# DAC.net
KiCad netlist of a schematic drawn in Altium Designer
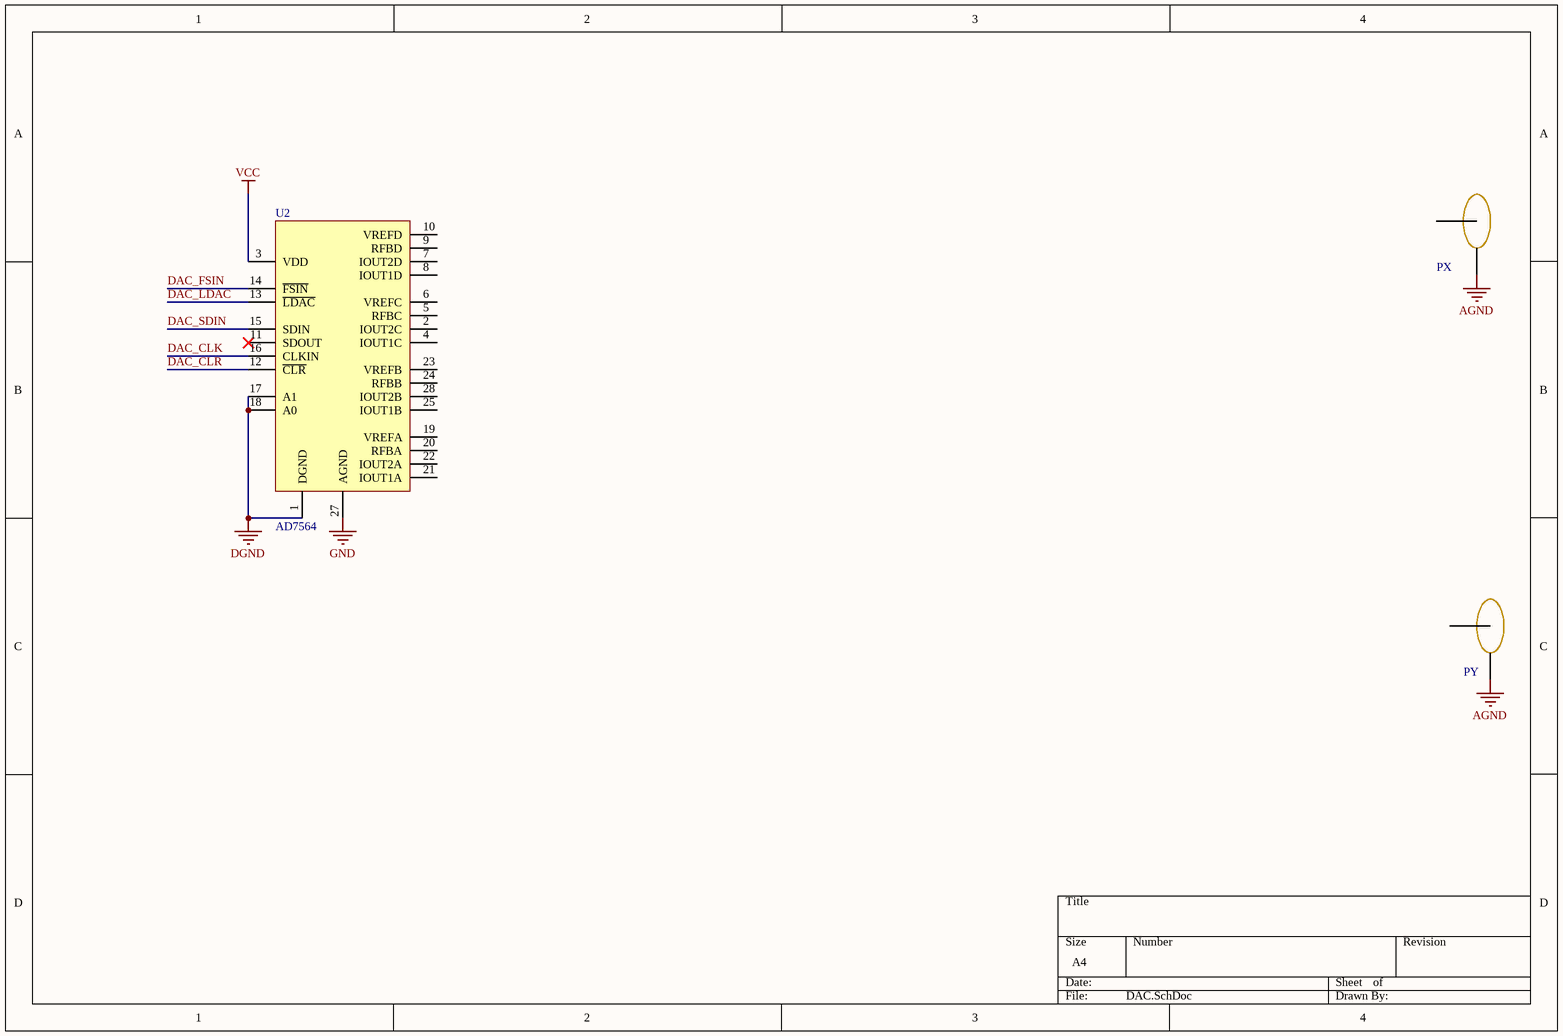
[diagram p0: DAC.SchDoc]

(export (version "E")
  (design (tool "Eeschema 10.0.6"))
  (components
    (comp (ref "PX")
      (value "PCB.SMAFRA.HT")
      (footprint "PCB.SMAFRA.HT")
      (libsource (lib "OpenSEM") (part "PCB.SMAFRA.HT"))
    )
    (comp (ref "PY")
      (value "PCB.SMAFRA.HT")
      (footprint "PCB.SMAFRA.HT")
      (libsource (lib "OpenSEM") (part "PCB.SMAFRA.HT"))
    )
    (comp (ref "U2")
      (value "AD7564")
      (footprint "AD7564")
      (description "+3.3 V/+5 V, Low Power, Quad 12-Bit DAC")
      (libsource (lib "OpenSEM") (part "AD7564"))
    )
  )
  (nets
    (net (code "1") (name "/DAC_CLK") (class "Default")
      (node (ref "U2") (pin "16") (pinfunction "CLKIN_16") (pintype "passive"))
    )
    (net (code "2") (name "/DAC_CLR") (class "Default")
      (node (ref "U2") (pin "12") (pinfunction "~{CLR}_12") (pintype "passive"))
    )
    (net (code "3") (name "/DAC_FSIN") (class "Default")
      (node (ref "U2") (pin "14") (pinfunction "~{FSIN}_14") (pintype "passive"))
    )
    (net (code "4") (name "/DAC_LDAC") (class "Default")
      (node (ref "U2") (pin "13") (pinfunction "~{LDAC}_13") (pintype "passive"))
    )
    (net (code "5") (name "/DAC_SDIN") (class "Default")
      (node (ref "U2") (pin "15") (pinfunction "SDIN_15") (pintype "passive"))
    )
    (net (code "6") (name "AGND") (class "Default")
      (node (ref "PX") (pin "S") (pinfunction "S_S") (pintype "passive"))
      (node (ref "PY") (pin "S") (pinfunction "S_S") (pintype "passive"))
    )
    (net (code "7") (name "DGND") (class "Default")
      (node (ref "U2") (pin "1") (pinfunction "DGND_1") (pintype "passive"))
      (node (ref "U2") (pin "17") (pinfunction "A1_17") (pintype "passive"))
      (node (ref "U2") (pin "18") (pinfunction "A0_18") (pintype "passive"))
    )
    (net (code "8") (name "GND") (class "Default")
      (node (ref "U2") (pin "27") (pinfunction "AGND_27") (pintype "passive"))
    )
    (net (code "9") (name "VCC") (class "Default")
      (node (ref "U2") (pin "3") (pinfunction "VDD_3") (pintype "passive"))
    )
    (net (code "10") (name "unconnected-(PX-Pad1)") (class "Default")
      (node (ref "PX") (pin "1") (pinfunction "1_1") (pintype "passive"))
    )
    (net (code "11") (name "unconnected-(PY-Pad1)") (class "Default")
      (node (ref "PY") (pin "1") (pinfunction "1_1") (pintype "passive"))
    )
    (net (code "12") (name "unconnected-(U2-IOUT1A-Pad21)") (class "Default")
      (node (ref "U2") (pin "21") (pinfunction "IOUT1A_21") (pintype "passive"))
    )
    (net (code "13") (name "unconnected-(U2-IOUT1B-Pad25)") (class "Default")
      (node (ref "U2") (pin "25") (pinfunction "IOUT1B_25") (pintype "passive"))
    )
    (net (code "14") (name "unconnected-(U2-IOUT1C-Pad4)") (class "Default")
      (node (ref "U2") (pin "4") (pinfunction "IOUT1C_4") (pintype "passive"))
    )
    (net (code "15") (name "unconnected-(U2-IOUT1D-Pad8)") (class "Default")
      (node (ref "U2") (pin "8") (pinfunction "IOUT1D_8") (pintype "passive"))
    )
    (net (code "16") (name "unconnected-(U2-IOUT2A-Pad22)") (class "Default")
      (node (ref "U2") (pin "22") (pinfunction "IOUT2A_22") (pintype "passive"))
    )
    (net (code "17") (name "unconnected-(U2-IOUT2B-Pad28)") (class "Default")
      (node (ref "U2") (pin "28") (pinfunction "IOUT2B_28") (pintype "passive"))
    )
    (net (code "18") (name "unconnected-(U2-IOUT2C-Pad2)") (class "Default")
      (node (ref "U2") (pin "2") (pinfunction "IOUT2C_2") (pintype "passive"))
    )
    (net (code "19") (name "unconnected-(U2-IOUT2D-Pad7)") (class "Default")
      (node (ref "U2") (pin "7") (pinfunction "IOUT2D_7") (pintype "passive"))
    )
    (net (code "20") (name "unconnected-(U2-RFBA-Pad20)") (class "Default")
      (node (ref "U2") (pin "20") (pinfunction "RFBA_20") (pintype "passive"))
    )
    (net (code "21") (name "unconnected-(U2-RFBB-Pad24)") (class "Default")
      (node (ref "U2") (pin "24") (pinfunction "RFBB_24") (pintype "passive"))
    )
    (net (code "22") (name "unconnected-(U2-RFBC-Pad5)") (class "Default")
      (node (ref "U2") (pin "5") (pinfunction "RFBC_5") (pintype "passive"))
    )
    (net (code "23") (name "unconnected-(U2-RFBD-Pad9)") (class "Default")
      (node (ref "U2") (pin "9") (pinfunction "RFBD_9") (pintype "passive"))
    )
    (net (code "24") (name "unconnected-(U2-SDOUT-Pad11)") (class "Default")
      (node (ref "U2") (pin "11") (pinfunction "SDOUT_11") (pintype "passive+no_connect"))
    )
    (net (code "25") (name "unconnected-(U2-VREFA-Pad19)") (class "Default")
      (node (ref "U2") (pin "19") (pinfunction "VREFA_19") (pintype "passive"))
    )
    (net (code "26") (name "unconnected-(U2-VREFB-Pad23)") (class "Default")
      (node (ref "U2") (pin "23") (pinfunction "VREFB_23") (pintype "passive"))
    )
    (net (code "27") (name "unconnected-(U2-VREFC-Pad6)") (class "Default")
      (node (ref "U2") (pin "6") (pinfunction "VREFC_6") (pintype "passive"))
    )
    (net (code "28") (name "unconnected-(U2-VREFD-Pad10)") (class "Default")
      (node (ref "U2") (pin "10") (pinfunction "VREFD_10") (pintype "passive"))
    )
  )
)
